# PowerSup.net
KiCad netlist of a schematic drawn in Altium Designer
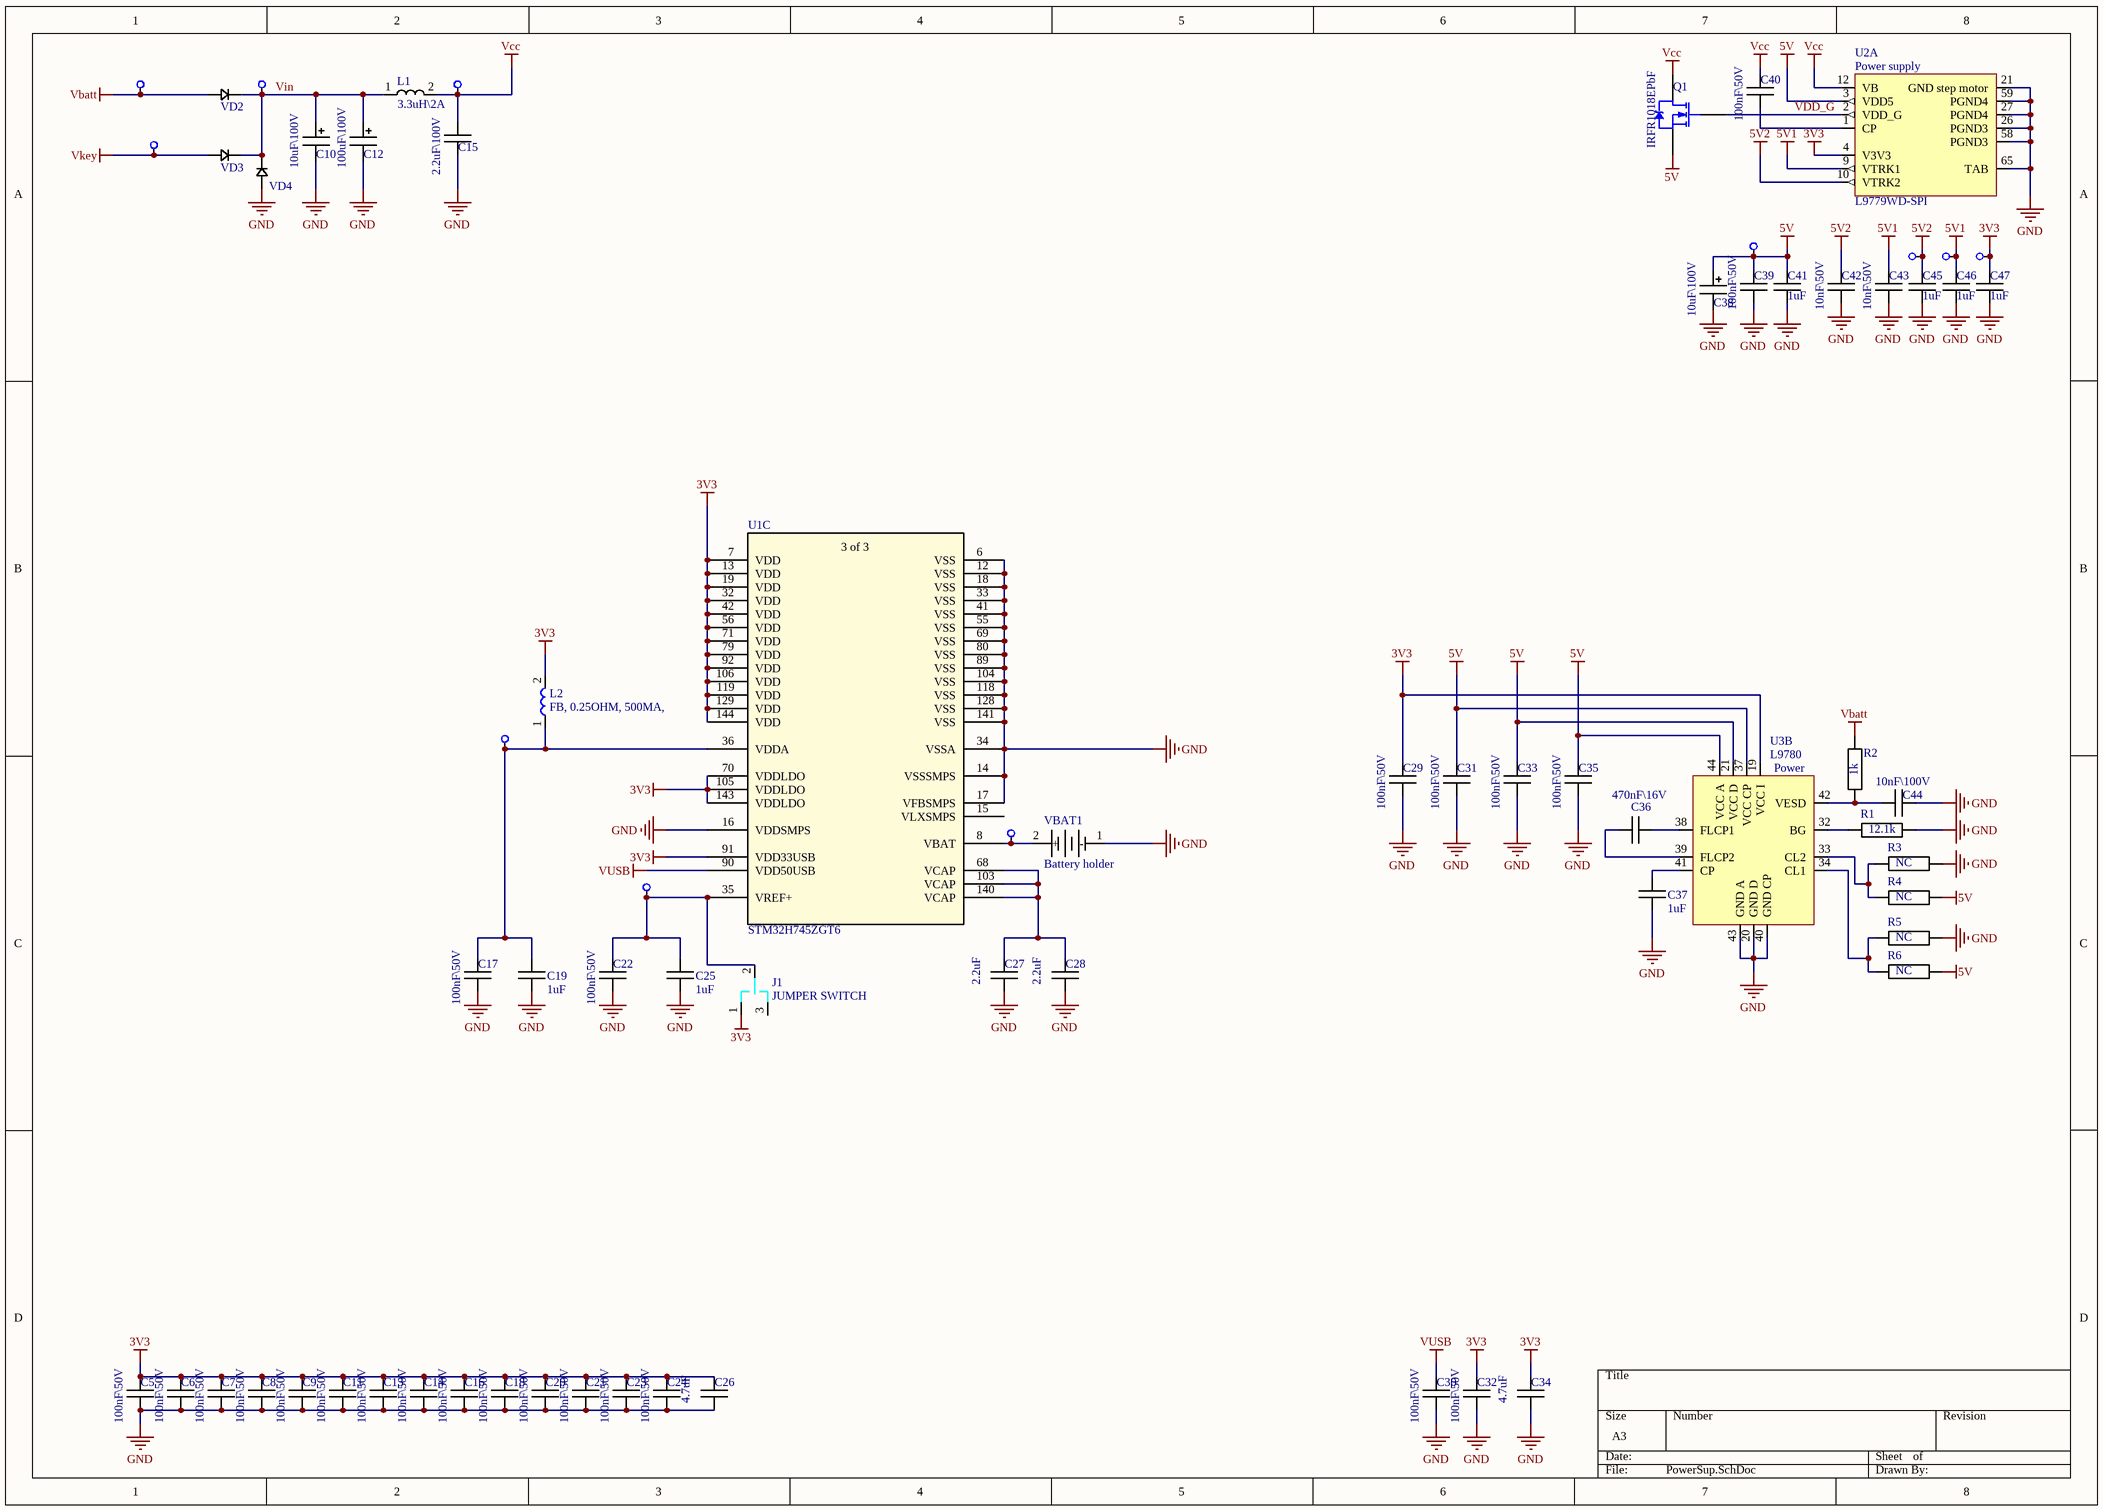
[diagram p0: PowerSup.SchDoc]

(export (version "E")
  (design (tool "Eeschema 10.0.6"))
  (components
    (comp (ref "C5")
      (value "100n~{F}50V")
      (footprint "SMD 0603")
      (description "CC0603KRX7R9BB104")
      (libsource (lib "Maks_lib") (part "Capasitor"))
    )
    (comp (ref "C6")
      (value "100n~{F}50V")
      (footprint "SMD 0603")
      (description "CC0603KRX7R9BB104")
      (libsource (lib "Maks_lib") (part "Capasitor"))
    )
    (comp (ref "C7")
      (value "100n~{F}50V")
      (footprint "SMD 0603")
      (description "CC0603KRX7R9BB104")
      (libsource (lib "Maks_lib") (part "Capasitor"))
    )
    (comp (ref "C8")
      (value "100n~{F}50V")
      (footprint "SMD 0603")
      (description "CC0603KRX7R9BB104")
      (libsource (lib "Maks_lib") (part "Capasitor"))
    )
    (comp (ref "C9")
      (value "100n~{F}50V")
      (footprint "SMD 0603")
      (description "CC0603KRX7R9BB104")
      (libsource (lib "Maks_lib") (part "Capasitor"))
    )
    (comp (ref "C10")
      (value "10u~{F}100V")
      (footprint "CAP 5x11")
      (description "SH100M0010BZF-0611")
      (libsource (lib "Maks_lib") (part "Capasitor polar"))
    )
    (comp (ref "C11")
      (value "100n~{F}50V")
      (footprint "SMD 0603")
      (description "CC0603KRX7R9BB104")
      (libsource (lib "Maks_lib") (part "Capasitor"))
    )
    (comp (ref "C12")
      (value "100u~{F}100V")
      (footprint "CAP 10x20")
      (description "SK100M0100B5S-1019")
      (libsource (lib "Maks_lib") (part "Capasitor polar"))
    )
    (comp (ref "C13")
      (value "100n~{F}50V")
      (footprint "SMD 0603")
      (description "CC0603KRX7R9BB104")
      (libsource (lib "Maks_lib") (part "Capasitor"))
    )
    (comp (ref "C14")
      (value "100n~{F}50V")
      (footprint "SMD 0603")
      (description "CC0603KRX7R9BB104")
      (libsource (lib "Maks_lib") (part "Capasitor"))
    )
    (comp (ref "C15")
      (value "2.2u~{F}100V")
      (footprint "SMD 1206")
      (description "GRM31CR72A225KA73L")
      (libsource (lib "Maks_lib") (part "Capasitor"))
    )
    (comp (ref "C16")
      (value "100n~{F}50V")
      (footprint "SMD 0603")
      (description "CC0603KRX7R9BB104")
      (libsource (lib "Maks_lib") (part "Capasitor"))
    )
    (comp (ref "C17")
      (value "100n~{F}50V")
      (footprint "SMD 0603")
      (description "CC0603KRX7R9BB104")
      (libsource (lib "Maks_lib") (part "Capasitor"))
    )
    (comp (ref "C18")
      (value "100n~{F}50V")
      (footprint "SMD 0603")
      (description "CC0603KRX7R9BB104")
      (libsource (lib "Maks_lib") (part "Capasitor"))
    )
    (comp (ref "C19")
      (value "1uF")
      (footprint "SMD 0603")
      (description "CL10A105KB8NNNC")
      (libsource (lib "Maks_lib") (part "Capasitor"))
    )
    (comp (ref "C20")
      (value "100n~{F}50V")
      (footprint "SMD 0603")
      (description "CC0603KRX7R9BB104")
      (libsource (lib "Maks_lib") (part "Capasitor"))
    )
    (comp (ref "C21")
      (value "100n~{F}50V")
      (footprint "SMD 0603")
      (description "CC0603KRX7R9BB104")
      (libsource (lib "Maks_lib") (part "Capasitor"))
    )
    (comp (ref "C22")
      (value "100n~{F}50V")
      (footprint "SMD 0603")
      (description "CC0603KRX7R9BB104")
      (libsource (lib "Maks_lib") (part "Capasitor"))
    )
    (comp (ref "C23")
      (value "100n~{F}50V")
      (footprint "SMD 0603")
      (description "CC0603KRX7R9BB104")
      (libsource (lib "Maks_lib") (part "Capasitor"))
    )
    (comp (ref "C24")
      (value "100n~{F}50V")
      (footprint "SMD 0603")
      (description "CC0603KRX7R9BB104")
      (libsource (lib "Maks_lib") (part "Capasitor"))
    )
    (comp (ref "C25")
      (value "1uF")
      (footprint "SMD 0603")
      (description "CL10A105KB8NNNC")
      (libsource (lib "Maks_lib") (part "Capasitor"))
    )
    (comp (ref "C26")
      (value "4.7uF")
      (footprint "SMD 0603")
      (description "CC0603KRX5R6BB475")
      (libsource (lib "Maks_lib") (part "Capasitor"))
    )
    (comp (ref "C27")
      (value "2.2uF")
      (footprint "SMD 0603")
      (description "CC0603KRX5R6BB225")
      (libsource (lib "Maks_lib") (part "Capasitor"))
    )
    (comp (ref "C28")
      (value "2.2uF")
      (footprint "SMD 0603")
      (description "CC0603KRX5R6BB225")
      (libsource (lib "Maks_lib") (part "Capasitor"))
    )
    (comp (ref "C29")
      (value "100n~{F}50V")
      (footprint "SMD 0603")
      (description "CC0603KRX7R9BB104")
      (libsource (lib "Maks_lib") (part "Capasitor"))
    )
    (comp (ref "C30")
      (value "100n~{F}50V")
      (footprint "SMD 0603")
      (description "CC0603KRX7R9BB104")
      (libsource (lib "Maks_lib") (part "Capasitor"))
    )
    (comp (ref "C31")
      (value "100n~{F}50V")
      (footprint "SMD 0603")
      (description "CC0603KRX7R9BB104")
      (libsource (lib "Maks_lib") (part "Capasitor"))
    )
    (comp (ref "C32")
      (value "100n~{F}50V")
      (footprint "SMD 0603")
      (description "CC0603KRX7R9BB104")
      (libsource (lib "Maks_lib") (part "Capasitor"))
    )
    (comp (ref "C33")
      (value "100n~{F}50V")
      (footprint "SMD 0603")
      (description "CC0603KRX7R9BB104")
      (libsource (lib "Maks_lib") (part "Capasitor"))
    )
    (comp (ref "C34")
      (value "4.7uF")
      (footprint "SMD 0603")
      (description "CC0603KRX5R6BB475")
      (libsource (lib "Maks_lib") (part "Capasitor"))
    )
    (comp (ref "C35")
      (value "100n~{F}50V")
      (footprint "SMD 0603")
      (description "CC0603KRX7R9BB104")
      (libsource (lib "Maks_lib") (part "Capasitor"))
    )
    (comp (ref "C36")
      (value "470n~{F}16V")
      (footprint "SMD 0603")
      (description "CC0603KRX7R7BB474")
      (libsource (lib "Maks_lib") (part "Capasitor"))
    )
    (comp (ref "C37")
      (value "1uF")
      (footprint "SMD 0603")
      (description "CL10A105KB8NNNC")
      (libsource (lib "Maks_lib") (part "Capasitor"))
    )
    (comp (ref "C38")
      (value "10u~{F}100V")
      (footprint "CAP 5x11")
      (description "SH100M0010BZF-0611")
      (libsource (lib "Maks_lib") (part "Capasitor polar"))
    )
    (comp (ref "C39")
      (value "100n~{F}50V")
      (footprint "SMD 0603")
      (description "CC0603KRX7R9BB104")
      (libsource (lib "Maks_lib") (part "Capasitor"))
    )
    (comp (ref "C40")
      (value "100n~{F}50V")
      (footprint "SMD 0603")
      (description "CC0603KRX7R9BB104")
      (libsource (lib "Maks_lib") (part "Capasitor"))
    )
    (comp (ref "C41")
      (value "1uF")
      (footprint "SMD 0603")
      (description "CL10A105KB8NNNC")
      (libsource (lib "Maks_lib") (part "Capasitor"))
    )
    (comp (ref "C42")
      (value "10n~{F}50V")
      (footprint "SMD 0603")
      (description "CC0603JRX7R9BB103")
      (libsource (lib "Maks_lib") (part "Capasitor"))
    )
    (comp (ref "C43")
      (value "10n~{F}50V")
      (footprint "SMD 0603")
      (description "CC0603JRX7R9BB103")
      (libsource (lib "Maks_lib") (part "Capasitor"))
    )
    (comp (ref "C44")
      (value "10n~{F}100V")
      (footprint "SMD 0603")
      (description "CC0603KRX7R0BB103")
      (libsource (lib "Maks_lib") (part "Capasitor"))
    )
    (comp (ref "C45")
      (value "1uF")
      (footprint "SMD 0603")
      (description "CL10A105KB8NNNC")
      (libsource (lib "Maks_lib") (part "Capasitor"))
    )
    (comp (ref "C46")
      (value "1uF")
      (footprint "SMD 0603")
      (description "CL10A105KB8NNNC")
      (libsource (lib "Maks_lib") (part "Capasitor"))
    )
    (comp (ref "C47")
      (value "1uF")
      (footprint "SMD 0603")
      (description "CL10A105KB8NNNC")
      (libsource (lib "Maks_lib") (part "Capasitor"))
    )
    (comp (ref "J1")
      (value "JUMPER SWITCH")
      (footprint "JMP3")
      (libsource (lib "Maks_lib") (part "JUMPER SWITCH"))
    )
    (comp (ref "L1")
      (value "3.3u~{H}2A")
      (footprint "SDR0604")
      (description "SDR0604-3R3ML")
      (libsource (lib "Maks_lib") (part "Inductor"))
    )
    (comp (ref "L2")
      (value "FB, 0.25OHM, 500MA,")
      (footprint "SMD 0805")
      (description "BK2125HM601-T")
      (libsource (lib "Maks_lib") (part "Inductor"))
    )
    (comp (ref "Q1")
      (value "IRFR1018EPbF")
      (footprint "DPAK228P991X238-3M")
      (description "HEXFET Power MOSFET")
      (libsource (lib "Maks_lib") (part "IRFR1018EPbF"))
    )
    (comp (ref "R1")
      (value "12.1k")
      (footprint "SMD 0603")
      (description "RC0603FR-0712K1L")
      (libsource (lib "Maks_lib") (part "Resistor"))
    )
    (comp (ref "R2")
      (value "1k")
      (footprint "SMD 0603")
      (description "RC0603FR-071KL")
      (libsource (lib "Maks_lib") (part "Resistor"))
    )
    (comp (ref "R3") (value "NC") (footprint "SMD 0603") (libsource (lib "Maks_lib") (part "Resistor")))
    (comp (ref "R4") (value "NC") (footprint "SMD 0603") (libsource (lib "Maks_lib") (part "Resistor")))
    (comp (ref "R5") (value "NC") (footprint "SMD 0603") (libsource (lib "Maks_lib") (part "Resistor")))
    (comp (ref "R6") (value "NC") (footprint "SMD 0603") (libsource (lib "Maks_lib") (part "Resistor")))
    (comp (ref "TP18")
      (value "TestPoint")
      (footprint "TESTPOINT")
      (description "testPoint")
      (libsource (lib "Maks_lib") (part "TestPoint"))
    )
    (comp (ref "TP19")
      (value "TestPoint")
      (footprint "TESTPOINT")
      (description "testPoint")
      (libsource (lib "Maks_lib") (part "TestPoint"))
    )
    (comp (ref "TP20")
      (value "TestPoint")
      (footprint "TESTPOINT")
      (description "testPoint")
      (libsource (lib "Maks_lib") (part "TestPoint"))
    )
    (comp (ref "TP21")
      (value "TestPoint")
      (footprint "TESTPOINT")
      (description "testPoint")
      (libsource (lib "Maks_lib") (part "TestPoint"))
    )
    (comp (ref "TP22")
      (value "TestPoint")
      (footprint "TESTPOINT")
      (description "testPoint")
      (libsource (lib "Maks_lib") (part "TestPoint"))
    )
    (comp (ref "TP23")
      (value "TestPoint")
      (footprint "TESTPOINT")
      (description "testPoint")
      (libsource (lib "Maks_lib") (part "TestPoint"))
    )
    (comp (ref "TP24")
      (value "TestPoint")
      (footprint "TESTPOINT")
      (description "testPoint")
      (libsource (lib "Maks_lib") (part "TestPoint"))
    )
    (comp (ref "TP25")
      (value "TestPoint")
      (footprint "TESTPOINT")
      (description "testPoint")
      (libsource (lib "Maks_lib") (part "TestPoint"))
    )
    (comp (ref "TP26")
      (value "TestPoint")
      (footprint "TESTPOINT")
      (description "testPoint")
      (libsource (lib "Maks_lib") (part "TestPoint"))
    )
    (comp (ref "TP27")
      (value "TestPoint")
      (footprint "TESTPOINT")
      (description "testPoint")
      (libsource (lib "Maks_lib") (part "TestPoint"))
    )
    (comp (ref "TP28")
      (value "TestPoint")
      (footprint "TESTPOINT")
      (description "testPoint")
      (libsource (lib "Maks_lib") (part "TestPoint"))
    )
    (comp (ref "U1")
      (value "STM32H745ZGT6")
      (footprint "LQFP-144")
      (description "No Description Available")
      (fields (field (name "COPYRIGHT") "Copyright (C) 2018 Accelerated Designs. All rights reserved"))
      (libsource (lib "STM32H745ZGT6") (part "STM32H745ZGT6"))
    )
    (comp (ref "U2")
      (value "L9779WD-SPI")
      (footprint "HiQUAD-64")
      (description "Multifunction IC for engine management system")
      (libsource (lib "Maks_lib") (part "L9779WD-SPI"))
    )
    (comp (ref "U3")
      (value "L9780")
      (footprint "LQFP-48N")
      (description "Wide range air fuel sensor control interface")
      (libsource (lib "Maks_lib") (part "L9780"))
    )
    (comp (ref "VBAT1")
      (value "Battery holder")
      (footprint "796136-1")
      (libsource (lib "Maks_lib") (part "Battery holder"))
    )
    (comp (ref "VD2")
      (value "Diode")
      (footprint "DO-214AA")
      (description "STTH4R02U")
      (libsource (lib "Maks_lib") (part "Diode"))
    )
    (comp (ref "VD3")
      (value "Diode")
      (footprint "DO-214AA")
      (description "STTH4R02U 200 V, 4 A High Effiency Ultrafast Diode")
      (libsource (lib "Maks_lib") (part "Diode"))
    )
    (comp (ref "VD4")
      (value "Diode")
      (footprint "DO-214AB")
      (description "5.0SMDJ30CA")
      (libsource (lib "Maks_lib") (part "Diode"))
    )
  )
  (nets
    (net (code "1") (name "/VDD_G") (class "Default")
      (node (ref "Q1") (pin "1") (pinfunction "G_1") (pintype "passive"))
      (node (ref "U2") (pin "2") (pinfunction "VDD_G_2") (pintype "output"))
    )
    (net (code "2") (name "/Vin") (class "Default")
      (node (ref "C10") (pin "1") (pinfunction "1_1") (pintype "passive"))
      (node (ref "C12") (pin "1") (pinfunction "1_1") (pintype "passive"))
      (node (ref "L1") (pin "1") (pinfunction "1_1") (pintype "passive"))
      (node (ref "TP20") (pin "0") (pinfunction "0_0") (pintype "passive"))
      (node (ref "VD2") (pin "1") (pinfunction "1_1") (pintype "passive"))
      (node (ref "VD3") (pin "1") (pinfunction "1_1") (pintype "passive"))
      (node (ref "VD4") (pin "1") (pinfunction "1_1") (pintype "passive"))
    )
    (net (code "3") (name "3V3") (class "Default")
      (node (ref "C11") (pin "2") (pinfunction "2_2") (pintype "passive"))
      (node (ref "C13") (pin "2") (pinfunction "2_2") (pintype "passive"))
      (node (ref "C14") (pin "2") (pinfunction "2_2") (pintype "passive"))
      (node (ref "C16") (pin "2") (pinfunction "2_2") (pintype "passive"))
      (node (ref "C18") (pin "2") (pinfunction "2_2") (pintype "passive"))
      (node (ref "C20") (pin "2") (pinfunction "2_2") (pintype "passive"))
      (node (ref "C21") (pin "2") (pinfunction "2_2") (pintype "passive"))
      (node (ref "C23") (pin "2") (pinfunction "2_2") (pintype "passive"))
      (node (ref "C24") (pin "2") (pinfunction "2_2") (pintype "passive"))
      (node (ref "C26") (pin "2") (pinfunction "2_2") (pintype "passive"))
      (node (ref "C29") (pin "2") (pinfunction "2_2") (pintype "passive"))
      (node (ref "C32") (pin "2") (pinfunction "2_2") (pintype "passive"))
      (node (ref "C34") (pin "2") (pinfunction "2_2") (pintype "passive"))
      (node (ref "C47") (pin "2") (pinfunction "2_2") (pintype "passive"))
      (node (ref "C5") (pin "2") (pinfunction "2_2") (pintype "passive"))
      (node (ref "C6") (pin "2") (pinfunction "2_2") (pintype "passive"))
      (node (ref "C7") (pin "2") (pinfunction "2_2") (pintype "passive"))
      (node (ref "C8") (pin "2") (pinfunction "2_2") (pintype "passive"))
      (node (ref "C9") (pin "2") (pinfunction "2_2") (pintype "passive"))
      (node (ref "J1") (pin "1") (pintype "passive"))
      (node (ref "L2") (pin "2") (pinfunction "2_2") (pintype "passive"))
      (node (ref "TP28") (pin "0") (pinfunction "0_0") (pintype "passive"))
      (node (ref "U1") (pin "105") (pinfunction "VDDLDO_105") (pintype "power_in"))
      (node (ref "U1") (pin "106") (pinfunction "VDD_106") (pintype "power_in"))
      (node (ref "U1") (pin "119") (pinfunction "VDD_119") (pintype "power_in"))
      (node (ref "U1") (pin "129") (pinfunction "VDD_129") (pintype "power_in"))
      (node (ref "U1") (pin "13") (pinfunction "VDD_13") (pintype "power_in"))
      (node (ref "U1") (pin "143") (pinfunction "VDDLDO_143") (pintype "power_in"))
      (node (ref "U1") (pin "144") (pinfunction "VDD_144") (pintype "power_in"))
      (node (ref "U1") (pin "19") (pinfunction "VDD_19") (pintype "power_in"))
      (node (ref "U1") (pin "32") (pinfunction "VDD_32") (pintype "power_in"))
      (node (ref "U1") (pin "42") (pinfunction "VDD_42") (pintype "power_in"))
      (node (ref "U1") (pin "56") (pinfunction "VDD_56") (pintype "power_in"))
      (node (ref "U1") (pin "7") (pinfunction "VDD_7") (pintype "power_in"))
      (node (ref "U1") (pin "70") (pinfunction "VDDLDO_70") (pintype "power_in"))
      (node (ref "U1") (pin "71") (pinfunction "VDD_71") (pintype "power_in"))
      (node (ref "U1") (pin "79") (pinfunction "VDD_79") (pintype "power_in"))
      (node (ref "U1") (pin "91") (pinfunction "VDD33USB_91") (pintype "power_in"))
      (node (ref "U1") (pin "92") (pinfunction "VDD_92") (pintype "power_in"))
      (node (ref "U2") (pin "4") (pinfunction "V3V3_4") (pintype "power_in"))
      (node (ref "U3") (pin "19") (pinfunction "VCC_I_19") (pintype "passive"))
    )
    (net (code "4") (name "5V") (class "Default")
      (node (ref "C31") (pin "2") (pinfunction "2_2") (pintype "passive"))
      (node (ref "C33") (pin "2") (pinfunction "2_2") (pintype "passive"))
      (node (ref "C35") (pin "2") (pinfunction "2_2") (pintype "passive"))
      (node (ref "C38") (pin "1") (pinfunction "1_1") (pintype "passive"))
      (node (ref "C39") (pin "2") (pinfunction "2_2") (pintype "passive"))
      (node (ref "C41") (pin "2") (pinfunction "2_2") (pintype "passive"))
      (node (ref "Q1") (pin "3") (pinfunction "S_3") (pintype "passive"))
      (node (ref "R4") (pin "2") (pinfunction "2_2") (pintype "passive"))
      (node (ref "R6") (pin "2") (pinfunction "2_2") (pintype "passive"))
      (node (ref "TP25") (pin "0") (pinfunction "0_0") (pintype "passive"))
      (node (ref "U2") (pin "3") (pinfunction "VDD5_3") (pintype "output"))
      (node (ref "U3") (pin "21") (pinfunction "VCC_D_21") (pintype "passive"))
      (node (ref "U3") (pin "37") (pinfunction "VCC_CP_37") (pintype "passive"))
      (node (ref "U3") (pin "44") (pinfunction "VCC_A_44") (pintype "passive"))
    )
    (net (code "5") (name "5V1") (class "Default")
      (node (ref "C43") (pin "2") (pinfunction "2_2") (pintype "passive"))
      (node (ref "C46") (pin "2") (pinfunction "2_2") (pintype "passive"))
      (node (ref "TP27") (pin "0") (pinfunction "0_0") (pintype "passive"))
      (node (ref "U2") (pin "9") (pinfunction "VTRK1_9") (pintype "output"))
    )
    (net (code "6") (name "5V2") (class "Default")
      (node (ref "C42") (pin "2") (pinfunction "2_2") (pintype "passive"))
      (node (ref "C45") (pin "2") (pinfunction "2_2") (pintype "passive"))
      (node (ref "TP26") (pin "0") (pinfunction "0_0") (pintype "passive"))
      (node (ref "U2") (pin "10") (pinfunction "VTRK2_10") (pintype "output"))
    )
    (net (code "7") (name "GND") (class "Default")
      (node (ref "C10") (pin "0") (pinfunction "0_0") (pintype "passive"))
      (node (ref "C11") (pin "1") (pinfunction "1_1") (pintype "passive"))
      (node (ref "C12") (pin "0") (pinfunction "0_0") (pintype "passive"))
      (node (ref "C13") (pin "1") (pinfunction "1_1") (pintype "passive"))
      (node (ref "C14") (pin "1") (pinfunction "1_1") (pintype "passive"))
      (node (ref "C15") (pin "1") (pinfunction "1_1") (pintype "passive"))
      (node (ref "C16") (pin "1") (pinfunction "1_1") (pintype "passive"))
      (node (ref "C17") (pin "1") (pinfunction "1_1") (pintype "passive"))
      (node (ref "C18") (pin "1") (pinfunction "1_1") (pintype "passive"))
      (node (ref "C19") (pin "2") (pinfunction "2_2") (pintype "passive"))
      (node (ref "C20") (pin "1") (pinfunction "1_1") (pintype "passive"))
      (node (ref "C21") (pin "1") (pinfunction "1_1") (pintype "passive"))
      (node (ref "C22") (pin "1") (pinfunction "1_1") (pintype "passive"))
      (node (ref "C23") (pin "1") (pinfunction "1_1") (pintype "passive"))
      (node (ref "C24") (pin "1") (pinfunction "1_1") (pintype "passive"))
      (node (ref "C25") (pin "2") (pinfunction "2_2") (pintype "passive"))
      (node (ref "C26") (pin "1") (pinfunction "1_1") (pintype "passive"))
      (node (ref "C27") (pin "1") (pinfunction "1_1") (pintype "passive"))
      (node (ref "C28") (pin "1") (pinfunction "1_1") (pintype "passive"))
      (node (ref "C29") (pin "1") (pinfunction "1_1") (pintype "passive"))
      (node (ref "C30") (pin "1") (pinfunction "1_1") (pintype "passive"))
      (node (ref "C31") (pin "1") (pinfunction "1_1") (pintype "passive"))
      (node (ref "C32") (pin "1") (pinfunction "1_1") (pintype "passive"))
      (node (ref "C33") (pin "1") (pinfunction "1_1") (pintype "passive"))
      (node (ref "C34") (pin "1") (pinfunction "1_1") (pintype "passive"))
      (node (ref "C35") (pin "1") (pinfunction "1_1") (pintype "passive"))
      (node (ref "C37") (pin "2") (pinfunction "2_2") (pintype "passive"))
      (node (ref "C38") (pin "0") (pinfunction "0_0") (pintype "passive"))
      (node (ref "C39") (pin "1") (pinfunction "1_1") (pintype "passive"))
      (node (ref "C41") (pin "1") (pinfunction "1_1") (pintype "passive"))
      (node (ref "C42") (pin "1") (pinfunction "1_1") (pintype "passive"))
      (node (ref "C43") (pin "1") (pinfunction "1_1") (pintype "passive"))
      (node (ref "C44") (pin "1") (pinfunction "1_1") (pintype "passive"))
      (node (ref "C45") (pin "1") (pinfunction "1_1") (pintype "passive"))
      (node (ref "C46") (pin "1") (pinfunction "1_1") (pintype "passive"))
      (node (ref "C47") (pin "1") (pinfunction "1_1") (pintype "passive"))
      (node (ref "C5") (pin "1") (pinfunction "1_1") (pintype "passive"))
      (node (ref "C6") (pin "1") (pinfunction "1_1") (pintype "passive"))
      (node (ref "C7") (pin "1") (pinfunction "1_1") (pintype "passive"))
      (node (ref "C8") (pin "1") (pinfunction "1_1") (pintype "passive"))
      (node (ref "C9") (pin "1") (pinfunction "1_1") (pintype "passive"))
      (node (ref "R1") (pin "1") (pinfunction "1_1") (pintype "passive"))
      (node (ref "R3") (pin "1") (pinfunction "1_1") (pintype "passive"))
      (node (ref "R5") (pin "1") (pinfunction "1_1") (pintype "passive"))
      (node (ref "U1") (pin "104") (pinfunction "VSS_104") (pintype "passive"))
      (node (ref "U1") (pin "118") (pinfunction "VSS_118") (pintype "passive"))
      (node (ref "U1") (pin "12") (pinfunction "VSS_12") (pintype "passive"))
      (node (ref "U1") (pin "128") (pinfunction "VSS_128") (pintype "passive"))
      (node (ref "U1") (pin "14") (pinfunction "VSSSMPS_14") (pintype "passive"))
      (node (ref "U1") (pin "141") (pinfunction "VSS_141") (pintype "passive"))
      (node (ref "U1") (pin "16") (pinfunction "VDDSMPS_16") (pintype "power_in"))
      (node (ref "U1") (pin "17") (pinfunction "VFBSMPS_17") (pintype "passive"))
      (node (ref "U1") (pin "18") (pinfunction "VSS_18") (pintype "passive"))
      (node (ref "U1") (pin "33") (pinfunction "VSS_33") (pintype "passive"))
      (node (ref "U1") (pin "34") (pinfunction "VSSA_34") (pintype "passive"))
      (node (ref "U1") (pin "41") (pinfunction "VSS_41") (pintype "passive"))
      (node (ref "U1") (pin "55") (pinfunction "VSS_55") (pintype "passive"))
      (node (ref "U1") (pin "6") (pinfunction "VSS_6") (pintype "passive"))
      (node (ref "U1") (pin "69") (pinfunction "VSS_69") (pintype "passive"))
      (node (ref "U1") (pin "80") (pinfunction "VSS_80") (pintype "passive"))
      (node (ref "U1") (pin "89") (pinfunction "VSS_89") (pintype "passive"))
      (node (ref "U2") (pin "21") (pinfunction "GND_step_motor_21") (pintype "passive"))
      (node (ref "U2") (pin "26") (pinfunction "PGND3_26") (pintype "passive"))
      (node (ref "U2") (pin "27") (pinfunction "PGND4_27") (pintype "passive"))
      (node (ref "U2") (pin "58") (pinfunction "PGND3_58") (pintype "passive"))
      (node (ref "U2") (pin "59") (pinfunction "PGND4_59") (pintype "passive"))
      (node (ref "U2") (pin "65") (pinfunction "TAB_65") (pintype "passive"))
      (node (ref "U3") (pin "20") (pinfunction "GND_D_20") (pintype "passive"))
      (node (ref "U3") (pin "40") (pinfunction "GND_CP_40") (pintype "passive"))
      (node (ref "U3") (pin "43") (pinfunction "GND_A_43") (pintype "passive"))
      (node (ref "VBAT1") (pin "1") (pinfunction "-_1") (pintype "passive"))
      (node (ref "VD4") (pin "0") (pinfunction "0_0") (pintype "passive"))
    )
    (net (code "8") (name "Net-(C27-Pad2)") (class "Default")
      (node (ref "C27") (pin "2") (pinfunction "2_2") (pintype "passive"))
      (node (ref "C28") (pin "2") (pinfunction "2_2") (pintype "passive"))
      (node (ref "U1") (pin "103") (pinfunction "VCAP_103") (pintype "power_in"))
      (node (ref "U1") (pin "140") (pinfunction "VCAP_140") (pintype "power_in"))
      (node (ref "U1") (pin "68") (pinfunction "VCAP_68") (pintype "power_in"))
    )
    (net (code "9") (name "Net-(U1C-VBAT)") (class "Default")
      (node (ref "TP24") (pin "0") (pinfunction "0_0") (pintype "passive"))
      (node (ref "U1") (pin "8") (pinfunction "VBAT_8") (pintype "power_in"))
      (node (ref "VBAT1") (pin "2") (pinfunction "+_2") (pintype "passive"))
    )
    (net (code "10") (name "Net-(U1C-VDDA)") (class "Default")
      (node (ref "C17") (pin "2") (pinfunction "2_2") (pintype "passive"))
      (node (ref "C19") (pin "1") (pinfunction "1_1") (pintype "passive"))
      (node (ref "L2") (pin "1") (pinfunction "1_1") (pintype "passive"))
      (node (ref "TP22") (pin "0") (pinfunction "0_0") (pintype "passive"))
      (node (ref "U1") (pin "36") (pinfunction "VDDA_36") (pintype "power_in"))
    )
    (net (code "11") (name "Net-(U1C-VREF+)") (class "Default")
      (node (ref "C22") (pin "2") (pinfunction "2_2") (pintype "passive"))
      (node (ref "C25") (pin "1") (pinfunction "1_1") (pintype "passive"))
      (node (ref "J1") (pin "2") (pintype "passive"))
      (node (ref "TP23") (pin "0") (pinfunction "0_0") (pintype "passive"))
      (node (ref "U1") (pin "35") (pinfunction "VREF+_35") (pintype "power_in"))
    )
    (net (code "12") (name "Net-(U2A-CP)") (class "Default")
      (node (ref "C40") (pin "1") (pinfunction "1_1") (pintype "passive"))
      (node (ref "U2") (pin "1") (pinfunction "CP_1") (pintype "passive"))
    )
    (net (code "13") (name "Net-(U3B-BG)") (class "Default")
      (node (ref "R1") (pin "2") (pinfunction "2_2") (pintype "passive"))
      (node (ref "U3") (pin "32") (pinfunction "BG_32") (pintype "passive"))
    )
    (net (code "14") (name "Net-(U3B-CL1)") (class "Default")
      (node (ref "R5") (pin "2") (pinfunction "2_2") (pintype "passive"))
      (node (ref "R6") (pin "1") (pinfunction "1_1") (pintype "passive"))
      (node (ref "U3") (pin "34") (pinfunction "CL1_34") (pintype "passive"))
    )
    (net (code "15") (name "Net-(U3B-CL2)") (class "Default")
      (node (ref "R3") (pin "2") (pinfunction "2_2") (pintype "passive"))
      (node (ref "R4") (pin "1") (pinfunction "1_1") (pintype "passive"))
      (node (ref "U3") (pin "33") (pinfunction "CL2_33") (pintype "passive"))
    )
    (net (code "16") (name "Net-(U3B-CP)") (class "Default")
      (node (ref "C37") (pin "1") (pinfunction "1_1") (pintype "passive"))
      (node (ref "U3") (pin "41") (pinfunction "CP_41") (pintype "passive"))
    )
    (net (code "17") (name "Net-(U3B-FLCP1)") (class "Default")
      (node (ref "C36") (pin "1") (pinfunction "1_1") (pintype "passive"))
      (node (ref "U3") (pin "38") (pinfunction "FLCP1_38") (pintype "passive"))
    )
    (net (code "18") (name "Net-(U3B-FLCP2)") (class "Default")
      (node (ref "C36") (pin "2") (pinfunction "2_2") (pintype "passive"))
      (node (ref "U3") (pin "39") (pinfunction "FLCP2_39") (pintype "passive"))
    )
    (net (code "19") (name "Net-(U3B-VESD)") (class "Default")
      (node (ref "C44") (pin "2") (pinfunction "2_2") (pintype "passive"))
      (node (ref "R2") (pin "1") (pinfunction "1_1") (pintype "passive"))
      (node (ref "U3") (pin "42") (pinfunction "VESD_42") (pintype "passive"))
    )
    (net (code "20") (name "VUSB") (class "Default")
      (node (ref "C30") (pin "2") (pinfunction "2_2") (pintype "passive"))
      (node (ref "U1") (pin "90") (pinfunction "VDD50USB_90") (pintype "power_in"))
    )
    (net (code "21") (name "Vbatt") (class "Default")
      (node (ref "R2") (pin "2") (pinfunction "2_2") (pintype "passive"))
      (node (ref "TP18") (pin "0") (pinfunction "0_0") (pintype "passive"))
      (node (ref "VD2") (pin "0") (pinfunction "0_0") (pintype "passive"))
    )
    (net (code "22") (name "Vcc") (class "Default")
      (node (ref "C15") (pin "2") (pinfunction "2_2") (pintype "passive"))
      (node (ref "C40") (pin "2") (pinfunction "2_2") (pintype "passive"))
      (node (ref "L1") (pin "2") (pinfunction "2_2") (pintype "passive"))
      (node (ref "Q1") (pin "4") (pinfunction "D_4") (pintype "passive"))
      (node (ref "TP21") (pin "0") (pinfunction "0_0") (pintype "passive"))
      (node (ref "U2") (pin "12") (pinfunction "VB_12") (pintype "power_in"))
    )
    (net (code "23") (name "Vkey") (class "Default")
      (node (ref "TP19") (pin "0") (pinfunction "0_0") (pintype "passive"))
      (node (ref "VD3") (pin "0") (pinfunction "0_0") (pintype "passive"))
    )
    (net (code "24") (name "unconnected-(J1-Pad3)") (class "Default")
      (node (ref "J1") (pin "3") (pintype "passive"))
    )
    (net (code "25") (name "unconnected-(U1C-VLXSMPS-Pad15)") (class "Default")
      (node (ref "U1") (pin "15") (pinfunction "VLXSMPS_15") (pintype "power_in"))
    )
  )
)
